# EE3102_Project_2.net
KiCad netlist of a schematic drawn in Altium Designer
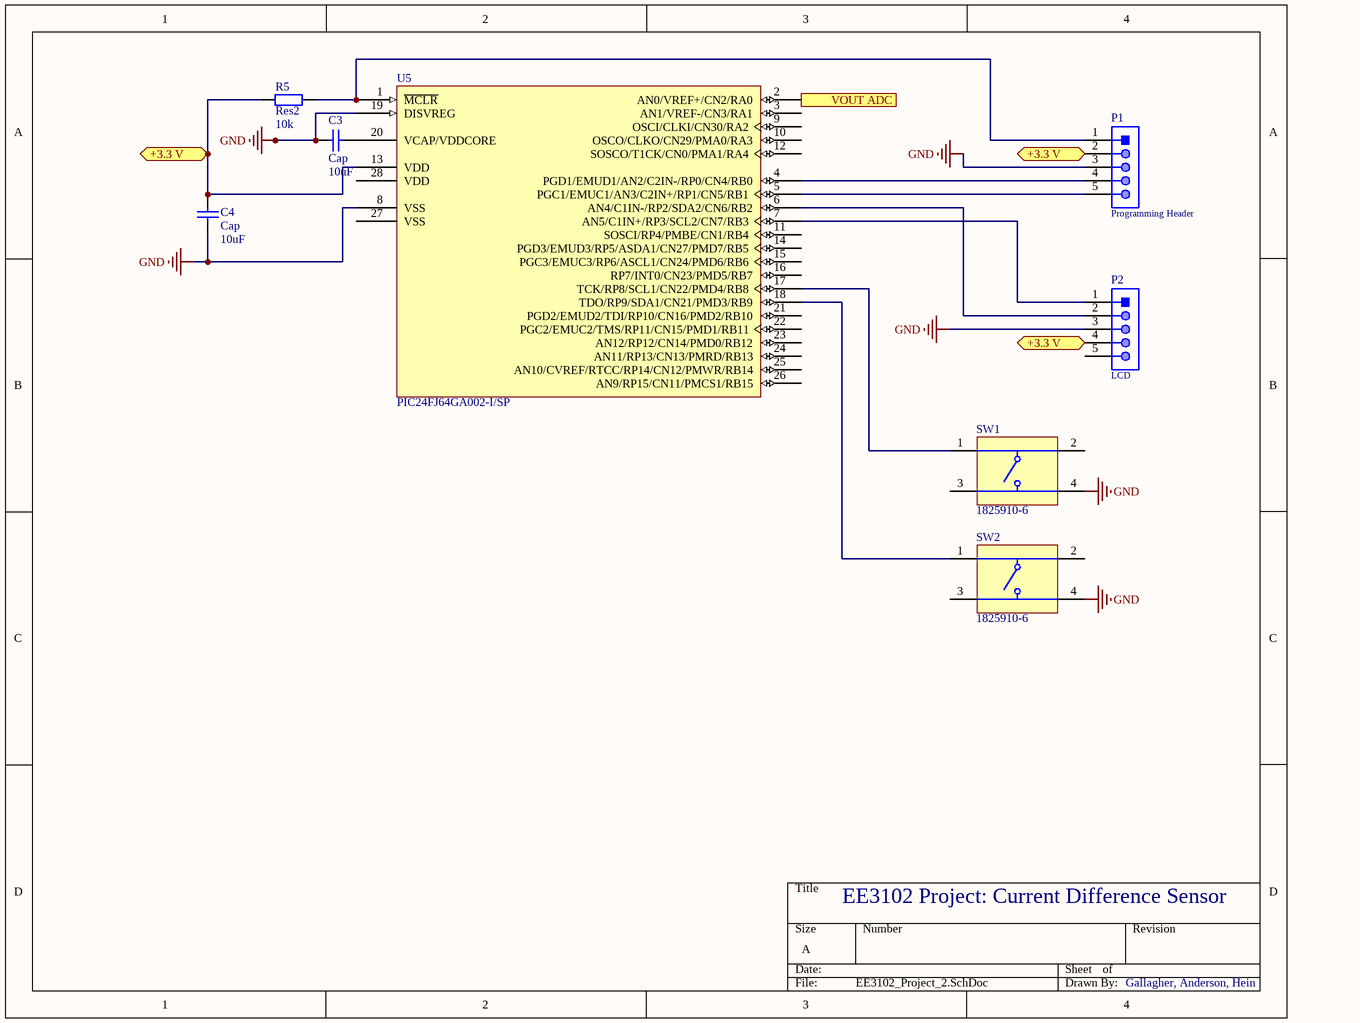
[diagram p0: EE3102_Project_2.SchDoc]

(export (version "E")
  (design (tool "Eeschema 10.0.6"))
  (components
    (comp (ref "C3")
      (value "Cap")
      (footprint "RAD-0.3")
      (description "Capacitor")
      (fields (field (name "ALTIUM_VALUE") "10uF") (field (name "PUBLISHER") "Altium Limited"))
      (libsource (lib "Miscellaneous Devices") (part "Cap"))
    )
    (comp (ref "C4")
      (value "Cap")
      (footprint "RAD-0.3")
      (description "Capacitor")
      (fields (field (name "ALTIUM_VALUE") "10uF") (field (name "PUBLISHER") "Altium Limited"))
      (libsource (lib "Miscellaneous Devices") (part "Cap"))
    )
    (comp (ref "P1")
      (value "Programming Header")
      (footprint "61300511121")
      (description "THT Vertical Pin Header WR-PHD, Pitch 2.54 mm, Single Row, 5 pins")
      (fields
        (field (name "PART NUMBER") "61300511121")
        (field (name "MANUFACTURER") "Wurth Elektronik")
        (field (name "PUBLISHER") "WurthElektronik")
      )
      (libsource (lib "Altium Content Vault") (part "WE-CN-1P-M-R5"))
    )
    (comp (ref "P2")
      (value "LCD")
      (footprint "LCD_5_Pin")
      (description "THT Vertical Pin Header WR-PHD, Pitch 2.54 mm, Single Row, 5 pins")
      (fields
        (field (name "PART NUMBER") "61300511121")
        (field (name "MANUFACTURER") "Wurth Elektronik")
        (field (name "PUBLISHER") "WurthElektronik")
      )
      (libsource (lib "Miscellaneous Devices") (part "WE-CN-1P-M-R5"))
    )
    (comp (ref "R5")
      (value "Res2")
      (footprint "AXIAL-0.4")
      (description "Resistor")
      (fields (field (name "ALTIUM_VALUE") "10k") (field (name "PUBLISHER") "Altium Limited"))
      (libsource (lib "Miscellaneous Devices") (part "Res2"))
    )
    (comp (ref "SW1")
      (value "1825910-6")
      (footprint "TECO-1825910-6_V")
      (description "Tact Switch, SPST-NO, 0.05 A, -35 to 85 degC, 4-Pin THD, RoHS, Bulk")
      (fields (field (name "MANUFACTURER") "TE Connectivity"))
      (libsource (lib "Altium Content Vault") (part "SW-SPST-4_A"))
    )
    (comp (ref "SW2")
      (value "1825910-6")
      (footprint "TECO-1825910-6_V")
      (description "Tact Switch, SPST-NO, 0.05 A, -35 to 85 degC, 4-Pin THD, RoHS, Bulk")
      (fields (field (name "MANUFACTURER") "TE Connectivity"))
      (libsource (lib "Altium Content Vault") (part "SW-SPST-4_A"))
    )
    (comp (ref "U5")
      (value "PIC24FJ64GA002-I/SP")
      (footprint "SPDIP300-SP28")
      (libsource (lib "Altium Content Vault") (part "MC-16B-16GA002-SOIC28"))
    )
  )
  (nets
    (net (code "1") (name "/+3.3 V") (class "Default")
      (node (ref "C4") (pin "1") (pinfunction "1_1") (pintype "passive"))
      (node (ref "P1") (pin "2") (pinfunction "VDD_2") (pintype "passive"))
      (node (ref "P2") (pin "4") (pinfunction "SDA_4") (pintype "passive"))
      (node (ref "R5") (pin "2") (pinfunction "2_2") (pintype "passive"))
      (node (ref "U5") (pin "13") (pinfunction "VDD_13") (pintype "power_in"))
    )
    (net (code "2") (name "/VOUT ADC") (class "Default")
      (node (ref "U5") (pin "2") (pinfunction "AN0/VREF+/CN2/RA0_2") (pintype "bidirectional"))
    )
    (net (code "3") (name "GND") (class "Default")
      (node (ref "C3") (pin "2") (pinfunction "2_2") (pintype "passive"))
      (node (ref "C4") (pin "2") (pinfunction "2_2") (pintype "passive"))
      (node (ref "P1") (pin "3") (pinfunction "VSS_3") (pintype "passive"))
      (node (ref "P2") (pin "3") (pinfunction "GND_3") (pintype "passive"))
      (node (ref "SW1") (pin "4") (pinfunction "4_4") (pintype "passive"))
      (node (ref "SW2") (pin "4") (pinfunction "4_4") (pintype "passive"))
      (node (ref "U5") (pin "19") (pinfunction "DISVREG_19") (pintype "input"))
      (node (ref "U5") (pin "8") (pinfunction "VSS_8") (pintype "power_in"))
    )
    (net (code "4") (name "Net-(P1-PGC)") (class "Default")
      (node (ref "P1") (pin "5") (pinfunction "PGC_5") (pintype "passive"))
      (node (ref "U5") (pin "5") (pinfunction "PGC1/EMUC1/AN3/C2IN+/RP1/CN5/RB1_5") (pintype "bidirectional"))
    )
    (net (code "5") (name "Net-(P1-PGD)") (class "Default")
      (node (ref "P1") (pin "4") (pinfunction "PGD_4") (pintype "passive"))
      (node (ref "U5") (pin "4") (pinfunction "PGD1/EMUD1/AN2/C2IN-/RP0/CN4/RB0_4") (pintype "bidirectional"))
    )
    (net (code "6") (name "Net-(P1-nmclr)") (class "Default")
      (node (ref "P1") (pin "1") (pinfunction "nmclr_1") (pintype "passive"))
      (node (ref "R5") (pin "1") (pinfunction "1_1") (pintype "passive"))
      (node (ref "U5") (pin "1") (pinfunction "~{MCLR}_1") (pintype "input"))
    )
    (net (code "7") (name "Net-(P2-VDD)") (class "Default")
      (node (ref "P2") (pin "2") (pinfunction "VDD_2") (pintype "passive"))
      (node (ref "U5") (pin "6") (pinfunction "AN4/C1IN-/RP2/SDA2/CN6/RB2_6") (pintype "bidirectional"))
    )
    (net (code "8") (name "Net-(P2-XRST)") (class "Default")
      (node (ref "P2") (pin "1") (pinfunction "XRST_1") (pintype "passive"))
      (node (ref "U5") (pin "7") (pinfunction "AN5/C1IN+/RP3/SCL2/CN7/RB3_7") (pintype "bidirectional"))
    )
    (net (code "9") (name "Net-(U5-TCK{slash}RP8{slash}SCL1{slash}CN22{slash}PMD4{slash}RB8)") (class "Default")
      (node (ref "SW1") (pin "1") (pinfunction "1_1") (pintype "passive"))
      (node (ref "U5") (pin "17") (pinfunction "TCK/RP8/SCL1/CN22/PMD4/RB8_17") (pintype "bidirectional"))
    )
    (net (code "10") (name "Net-(U5-TDO{slash}RP9{slash}SDA1{slash}CN21{slash}PMD3{slash}RB9)") (class "Default")
      (node (ref "SW2") (pin "1") (pinfunction "1_1") (pintype "passive"))
      (node (ref "U5") (pin "18") (pinfunction "TDO/RP9/SDA1/CN21/PMD3/RB9_18") (pintype "bidirectional"))
    )
    (net (code "11") (name "Net-(U5-VCAP{slash}VDDCORE)") (class "Default")
      (node (ref "C3") (pin "1") (pinfunction "1_1") (pintype "passive"))
      (node (ref "U5") (pin "20") (pinfunction "VCAP/VDDCORE_20") (pintype "power_in"))
    )
    (net (code "12") (name "unconnected-(P2-SCL-Pad5)") (class "Default")
      (node (ref "P2") (pin "5") (pinfunction "SCL_5") (pintype "passive"))
    )
    (net (code "13") (name "unconnected-(SW1-Pad2)") (class "Default")
      (node (ref "SW1") (pin "2") (pinfunction "2_2") (pintype "passive"))
    )
    (net (code "14") (name "unconnected-(SW1-Pad3)") (class "Default")
      (node (ref "SW1") (pin "3") (pinfunction "3_3") (pintype "passive"))
    )
    (net (code "15") (name "unconnected-(SW2-Pad2)") (class "Default")
      (node (ref "SW2") (pin "2") (pinfunction "2_2") (pintype "passive"))
    )
    (net (code "16") (name "unconnected-(SW2-Pad3)") (class "Default")
      (node (ref "SW2") (pin "3") (pinfunction "3_3") (pintype "passive"))
    )
    (net (code "17") (name "unconnected-(U5-AN1{slash}VREF-{slash}CN3{slash}RA1-Pad3)") (class "Default")
      (node (ref "U5") (pin "3") (pinfunction "AN1/VREF-/CN3/RA1_3") (pintype "bidirectional"))
    )
    (net (code "18") (name "unconnected-(U5-AN9{slash}RP15{slash}CN11{slash}PMCS1{slash}RB15-Pad26)") (class "Default")
      (node (ref "U5") (pin "26") (pinfunction "AN9/RP15/CN11/PMCS1/RB15_26") (pintype "bidirectional"))
    )
    (net (code "19") (name "unconnected-(U5-AN10{slash}CVREF{slash}RTCC{slash}RP14{slash}CN12{slash}PMWR{slash}RB14-Pad25)") (class "Default")
      (node (ref "U5") (pin "25") (pinfunction "AN10/CVREF/RTCC/RP14/CN12/PMWR/RB14_25") (pintype "bidirectional"))
    )
    (net (code "20") (name "unconnected-(U5-AN11{slash}RP13{slash}CN13{slash}PMRD{slash}RB13-Pad24)") (class "Default")
      (node (ref "U5") (pin "24") (pinfunction "AN11/RP13/CN13/PMRD/RB13_24") (pintype "bidirectional"))
    )
    (net (code "21") (name "unconnected-(U5-AN12{slash}RP12{slash}CN14{slash}PMD0{slash}RB12-Pad23)") (class "Default")
      (node (ref "U5") (pin "23") (pinfunction "AN12/RP12/CN14/PMD0/RB12_23") (pintype "bidirectional"))
    )
    (net (code "22") (name "unconnected-(U5-OSCI{slash}CLKI{slash}CN30{slash}RA2-Pad9)") (class "Default")
      (node (ref "U5") (pin "9") (pinfunction "OSCI/CLKI/CN30/RA2_9") (pintype "bidirectional"))
    )
    (net (code "23") (name "unconnected-(U5-OSCO{slash}CLKO{slash}CN29{slash}PMA0{slash}RA3-Pad10)") (class "Default")
      (node (ref "U5") (pin "10") (pinfunction "OSCO/CLKO/CN29/PMA0/RA3_10") (pintype "bidirectional"))
    )
    (net (code "24") (name "unconnected-(U5-PGC2{slash}EMUC2{slash}TMS{slash}RP11{slash}CN15{slash}PMD1{slash}RB11-Pad22)") (class "Default")
      (node (ref "U5") (pin "22") (pinfunction "PGC2/EMUC2/TMS/RP11/CN15/PMD1/RB11_22") (pintype "bidirectional"))
    )
    (net (code "25") (name "unconnected-(U5-PGC3{slash}EMUC3{slash}RP6{slash}ASCL1{slash}CN24{slash}PMD6{slash}RB6-Pad15)") (class "Default")
      (node (ref "U5") (pin "15") (pinfunction "PGC3/EMUC3/RP6/ASCL1/CN24/PMD6/RB6_15") (pintype "bidirectional"))
    )
    (net (code "26") (name "unconnected-(U5-PGD2{slash}EMUD2{slash}TDI{slash}RP10{slash}CN16{slash}PMD2{slash}RB10-Pad21)") (class "Default")
      (node (ref "U5") (pin "21") (pinfunction "PGD2/EMUD2/TDI/RP10/CN16/PMD2/RB10_21") (pintype "bidirectional"))
    )
    (net (code "27") (name "unconnected-(U5-PGD3{slash}EMUD3{slash}RP5{slash}ASDA1{slash}CN27{slash}PMD7{slash}RB5-Pad14)") (class "Default")
      (node (ref "U5") (pin "14") (pinfunction "PGD3/EMUD3/RP5/ASDA1/CN27/PMD7/RB5_14") (pintype "bidirectional"))
    )
    (net (code "28") (name "unconnected-(U5-RP7{slash}INT0{slash}CN23{slash}PMD5{slash}RB7-Pad16)") (class "Default")
      (node (ref "U5") (pin "16") (pinfunction "RP7/INT0/CN23/PMD5/RB7_16") (pintype "bidirectional"))
    )
    (net (code "29") (name "unconnected-(U5-SOSCI{slash}RP4{slash}PMBE{slash}CN1{slash}RB4-Pad11)") (class "Default")
      (node (ref "U5") (pin "11") (pinfunction "SOSCI/RP4/PMBE/CN1/RB4_11") (pintype "bidirectional"))
    )
    (net (code "30") (name "unconnected-(U5-SOSCO{slash}T1CK{slash}CN0{slash}PMA1{slash}RA4-Pad12)") (class "Default")
      (node (ref "U5") (pin "12") (pinfunction "SOSCO/T1CK/CN0/PMA1/RA4_12") (pintype "bidirectional"))
    )
    (net (code "31") (name "unconnected-(U5-VDD-Pad28)") (class "Default")
      (node (ref "U5") (pin "28") (pinfunction "VDD_28") (pintype "power_in"))
    )
    (net (code "32") (name "unconnected-(U5-VSS-Pad27)") (class "Default")
      (node (ref "U5") (pin "27") (pinfunction "VSS_27") (pintype "power_in"))
    )
  )
)
